# L9110.net
KiCad netlist of a schematic drawn in Altium Designer
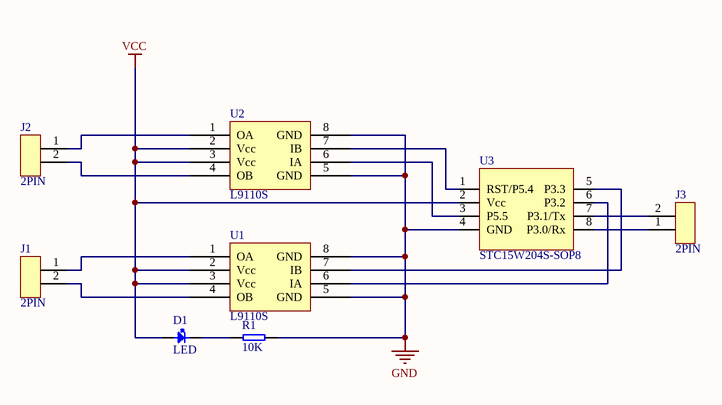
[diagram p0: L9110.SchDoc]

(export (version "E")
  (design (tool "Eeschema 10.0.6"))
  (components
    (comp (ref "D1") (value "LED") (footprint "LED0805") (libsource (lib "MaWei") (part "LED")))
    (comp (ref "J1") (value "2PIN") (footprint "2PIN") (libsource (lib "") (part "2PIN_1")))
    (comp (ref "J2") (value "2PIN") (footprint "2PIN") (libsource (lib "") (part "2PIN_1")))
    (comp (ref "J3") (value "2PIN") (footprint "2PIN") (libsource (lib "MaWei") (part "2PIN")))
    (comp (ref "R1") (value "10K") (footprint "RES0603") (libsource (lib "MaWei") (part "RES")))
    (comp (ref "U1") (value "L9110S") (footprint "SOP8") (libsource (lib "MaWei") (part "L9110S")))
    (comp (ref "U2") (value "L9110S") (footprint "SOP8") (libsource (lib "MaWei") (part "L9110S")))
    (comp (ref "U3") (value "STC15W204S-SOP8") (libsource (lib "MaWei") (part "STC15W204S-SOP8")))
  )
  (nets
    (net (code "1") (name "GND") (class "Default")
      (node (ref "R1") (pin "2") (pinfunction "2_2") (pintype "passive"))
      (node (ref "U1") (pin "5") (pinfunction "GND_5") (pintype "passive"))
      (node (ref "U1") (pin "8") (pinfunction "GND_8") (pintype "passive"))
      (node (ref "U2") (pin "5") (pinfunction "GND_5") (pintype "passive"))
      (node (ref "U2") (pin "8") (pinfunction "GND_8") (pintype "passive"))
      (node (ref "U3") (pin "4") (pinfunction "GND_4") (pintype "passive"))
    )
    (net (code "2") (name "Net-(D1-K)") (class "Default")
      (node (ref "D1") (pin "2") (pinfunction "K_2") (pintype "passive"))
      (node (ref "R1") (pin "1") (pinfunction "1_1") (pintype "passive"))
    )
    (net (code "3") (name "Net-(U1-IA)") (class "Default")
      (node (ref "U1") (pin "6") (pinfunction "IA_6") (pintype "passive"))
      (node (ref "U3") (pin "6") (pinfunction "P3.2_6") (pintype "passive"))
    )
    (net (code "4") (name "Net-(U1-IB)") (class "Default")
      (node (ref "U1") (pin "7") (pinfunction "IB_7") (pintype "passive"))
      (node (ref "U3") (pin "5") (pinfunction "P3.3_5") (pintype "passive"))
    )
    (net (code "5") (name "Net-(U1-OA)") (class "Default")
      (node (ref "J1") (pin "1") (pinfunction "1_1") (pintype "passive"))
      (node (ref "U1") (pin "1") (pinfunction "OA_1") (pintype "passive"))
    )
    (net (code "6") (name "Net-(U1-OB)") (class "Default")
      (node (ref "J1") (pin "2") (pinfunction "2_2") (pintype "passive"))
      (node (ref "U1") (pin "4") (pinfunction "OB_4") (pintype "passive"))
    )
    (net (code "7") (name "Net-(U2-IA)") (class "Default")
      (node (ref "U2") (pin "6") (pinfunction "IA_6") (pintype "passive"))
      (node (ref "U3") (pin "3") (pinfunction "P5.5_3") (pintype "passive"))
    )
    (net (code "8") (name "Net-(U2-IB)") (class "Default")
      (node (ref "U2") (pin "7") (pinfunction "IB_7") (pintype "passive"))
      (node (ref "U3") (pin "1") (pinfunction "RST/P5.4_1") (pintype "passive"))
    )
    (net (code "9") (name "Net-(U2-OA)") (class "Default")
      (node (ref "J2") (pin "1") (pinfunction "1_1") (pintype "passive"))
      (node (ref "U2") (pin "1") (pinfunction "OA_1") (pintype "passive"))
    )
    (net (code "10") (name "Net-(U2-OB)") (class "Default")
      (node (ref "J2") (pin "2") (pinfunction "2_2") (pintype "passive"))
      (node (ref "U2") (pin "4") (pinfunction "OB_4") (pintype "passive"))
    )
    (net (code "11") (name "Net-(U3-P3.0{slash}Rx)") (class "Default")
      (node (ref "J3") (pin "1") (pinfunction "1_1") (pintype "passive"))
      (node (ref "U3") (pin "8") (pinfunction "P3.0/Rx_8") (pintype "passive"))
    )
    (net (code "12") (name "Net-(U3-P3.1{slash}Tx)") (class "Default")
      (node (ref "J3") (pin "2") (pinfunction "2_2") (pintype "passive"))
      (node (ref "U3") (pin "7") (pinfunction "P3.1/Tx_7") (pintype "passive"))
    )
    (net (code "13") (name "VCC") (class "Default")
      (node (ref "D1") (pin "1") (pinfunction "A_1") (pintype "passive"))
      (node (ref "U1") (pin "2") (pinfunction "Vcc_2") (pintype "passive"))
      (node (ref "U1") (pin "3") (pinfunction "Vcc_3") (pintype "passive"))
      (node (ref "U2") (pin "2") (pinfunction "Vcc_2") (pintype "passive"))
      (node (ref "U2") (pin "3") (pinfunction "Vcc_3") (pintype "passive"))
      (node (ref "U3") (pin "2") (pinfunction "Vcc_2") (pintype "passive"))
    )
  )
)
